# LTC6803-3.net
KiCad netlist of a schematic drawn in Altium Designer
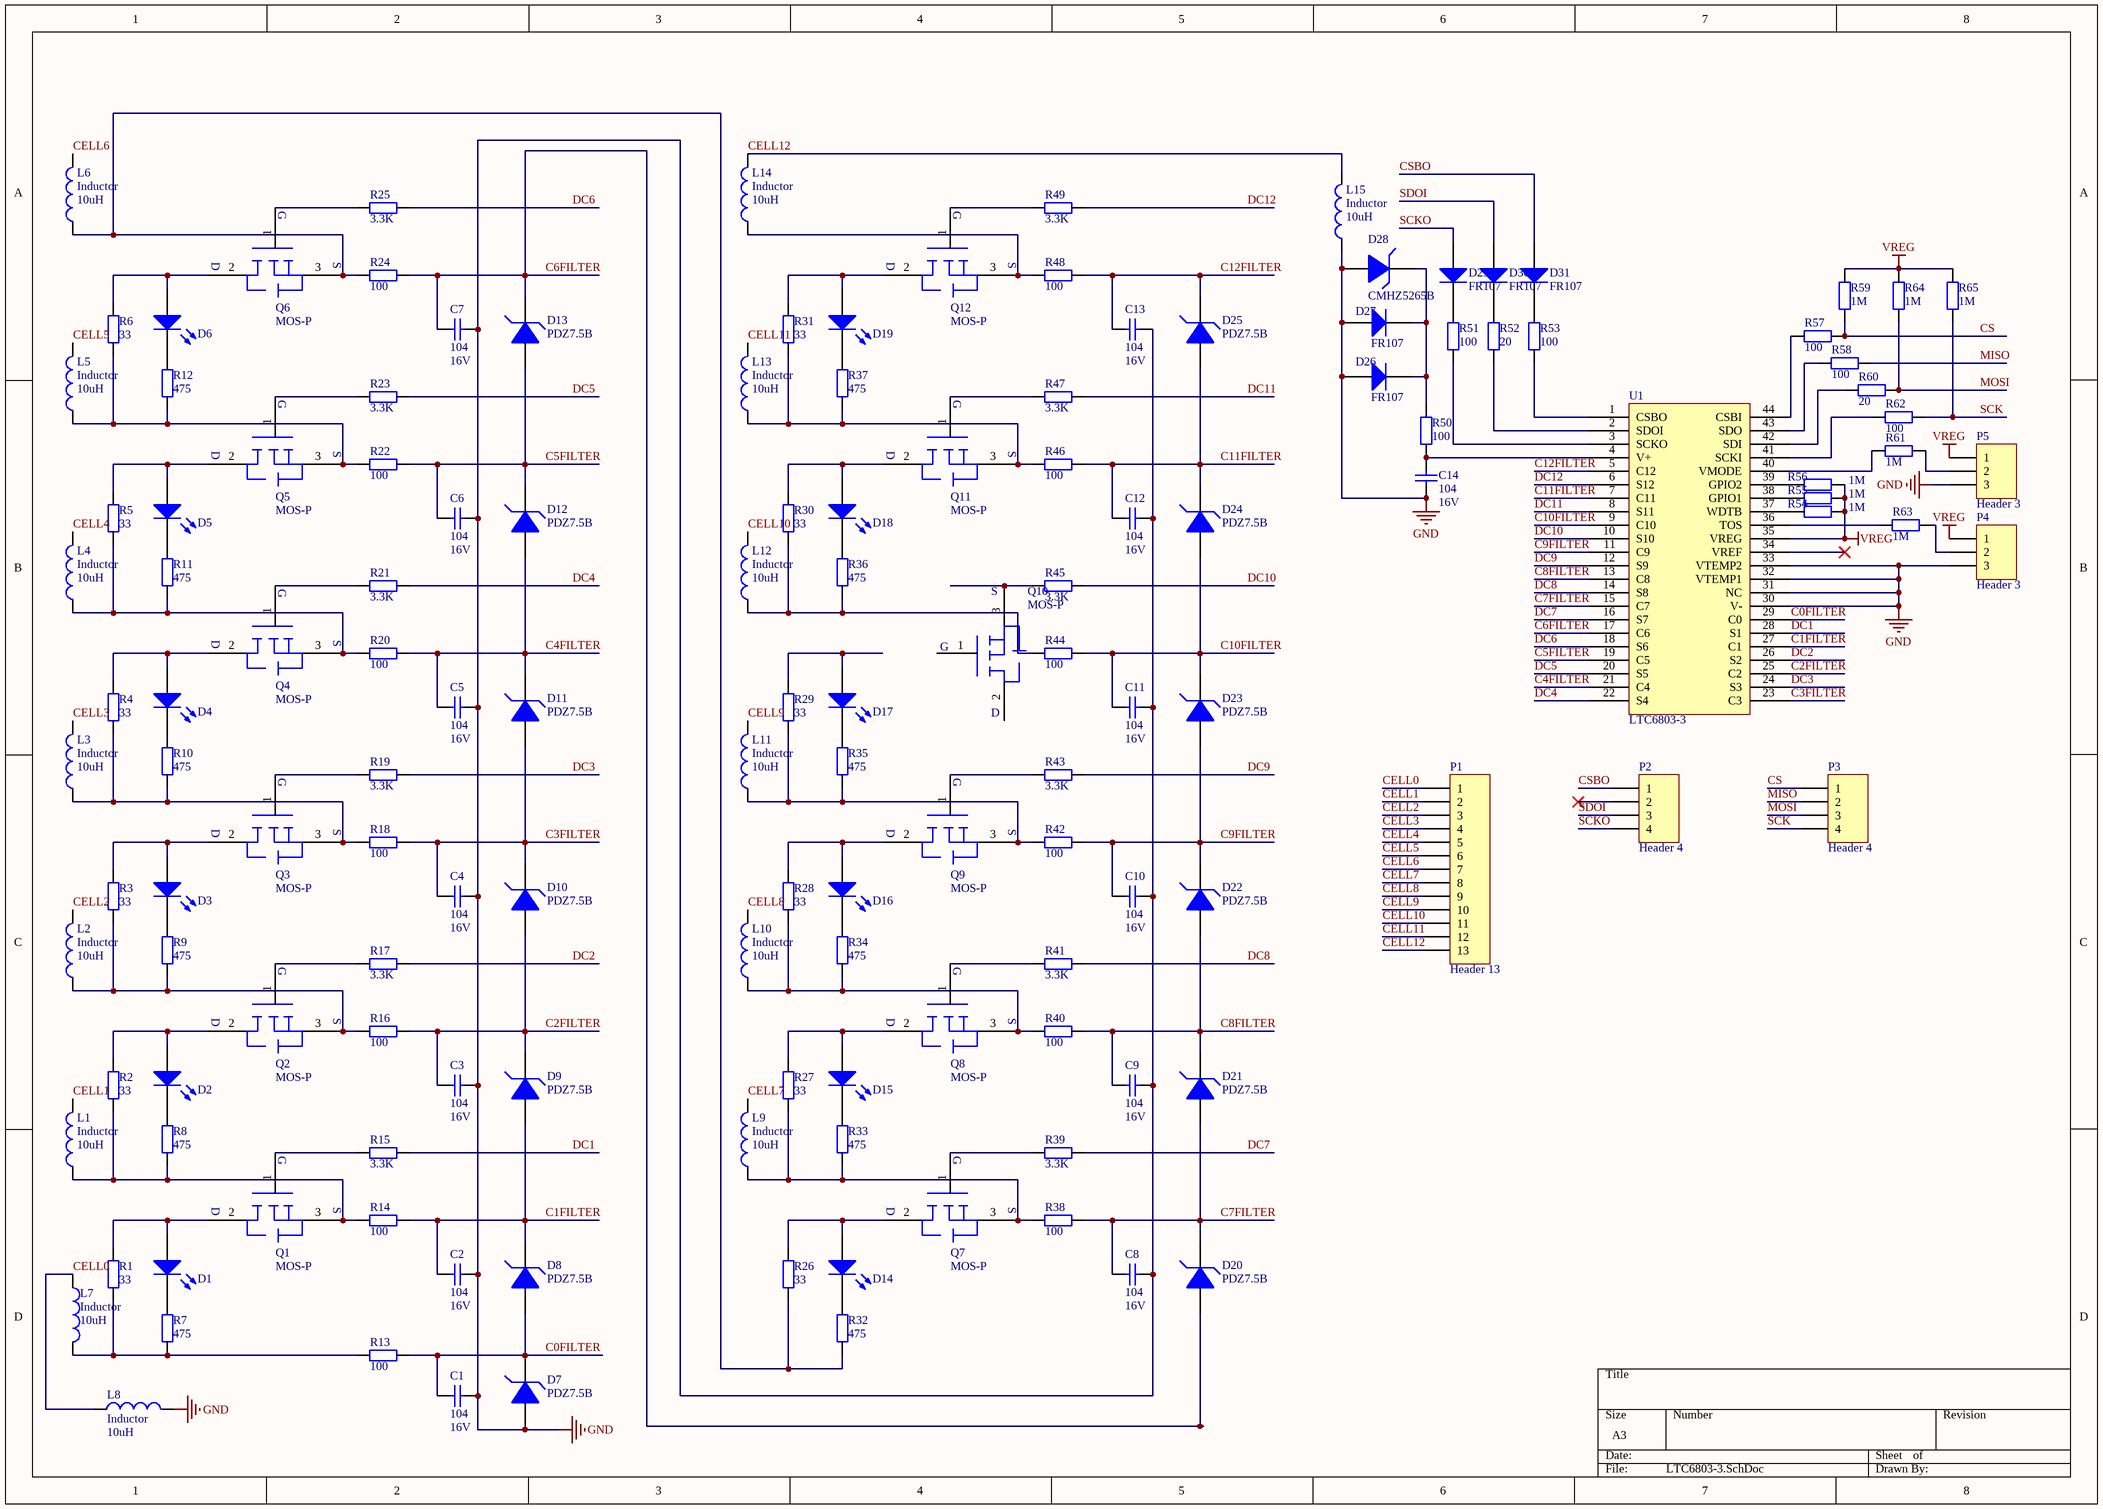
[diagram p0: LTC6803-3.SchDoc]

(export (version "E")
  (design (tool "Eeschema 10.0.6"))
  (components
    (comp (ref "C1")
      (value "104")
      (footprint "1206")
      (fields (field (name "PRESSURE VOLTAGE") "16V") (field (name "Comment") "Cap"))
      (libsource (lib "自动化研究所集成库20170403") (part "Cap"))
    )
    (comp (ref "C2")
      (value "104")
      (footprint "1206")
      (fields (field (name "PRESSURE VOLTAGE") "16V") (field (name "Comment") "Cap"))
      (libsource (lib "自动化研究所集成库20170403") (part "Cap"))
    )
    (comp (ref "C3")
      (value "104")
      (footprint "1206")
      (fields (field (name "PRESSURE VOLTAGE") "16V") (field (name "Comment") "Cap"))
      (libsource (lib "自动化研究所集成库20170403") (part "Cap"))
    )
    (comp (ref "C4")
      (value "104")
      (footprint "1206")
      (fields (field (name "PRESSURE VOLTAGE") "16V") (field (name "Comment") "Cap"))
      (libsource (lib "自动化研究所集成库20170403") (part "Cap"))
    )
    (comp (ref "C5")
      (value "104")
      (footprint "1206")
      (fields (field (name "PRESSURE VOLTAGE") "16V") (field (name "Comment") "Cap"))
      (libsource (lib "自动化研究所集成库20170403") (part "Cap"))
    )
    (comp (ref "C6")
      (value "104")
      (footprint "1206")
      (fields (field (name "PRESSURE VOLTAGE") "16V") (field (name "Comment") "Cap"))
      (libsource (lib "自动化研究所集成库20170403") (part "Cap"))
    )
    (comp (ref "C7")
      (value "104")
      (footprint "1206")
      (fields (field (name "PRESSURE VOLTAGE") "16V") (field (name "Comment") "Cap"))
      (libsource (lib "自动化研究所集成库20170403") (part "Cap"))
    )
    (comp (ref "C8")
      (value "104")
      (footprint "1206")
      (fields (field (name "PRESSURE VOLTAGE") "16V") (field (name "Comment") "Cap"))
      (libsource (lib "自动化研究所集成库20170403") (part "Cap"))
    )
    (comp (ref "C9")
      (value "104")
      (footprint "1206")
      (fields (field (name "PRESSURE VOLTAGE") "16V") (field (name "Comment") "Cap"))
      (libsource (lib "自动化研究所集成库20170403") (part "Cap"))
    )
    (comp (ref "C10")
      (value "104")
      (footprint "1206")
      (fields (field (name "PRESSURE VOLTAGE") "16V") (field (name "Comment") "Cap"))
      (libsource (lib "自动化研究所集成库20170403") (part "Cap"))
    )
    (comp (ref "C11")
      (value "104")
      (footprint "1206")
      (fields (field (name "PRESSURE VOLTAGE") "16V") (field (name "Comment") "Cap"))
      (libsource (lib "自动化研究所集成库20170403") (part "Cap"))
    )
    (comp (ref "C12")
      (value "104")
      (footprint "1206")
      (fields (field (name "PRESSURE VOLTAGE") "16V") (field (name "Comment") "Cap"))
      (libsource (lib "自动化研究所集成库20170403") (part "Cap"))
    )
    (comp (ref "C13")
      (value "104")
      (footprint "1206")
      (fields (field (name "PRESSURE VOLTAGE") "16V") (field (name "Comment") "Cap"))
      (libsource (lib "自动化研究所集成库20170403") (part "Cap"))
    )
    (comp (ref "C14")
      (value "104")
      (footprint "1206")
      (fields (field (name "PRESSURE VOLTAGE") "16V") (field (name "Comment") "Cap"))
      (libsource (lib "自动化研究所集成库20170403") (part "Cap"))
    )
    (comp (ref "D1") (value "LED") (footprint "LED_0805") (libsource (lib "自动化研究所集成库20170403") (part "LED")))
    (comp (ref "D2") (value "LED") (footprint "LED_0805") (libsource (lib "自动化研究所集成库20170403") (part "LED")))
    (comp (ref "D3") (value "LED") (footprint "LED_0805") (libsource (lib "自动化研究所集成库20170403") (part "LED")))
    (comp (ref "D4") (value "LED") (footprint "LED_0805") (libsource (lib "自动化研究所集成库20170403") (part "LED")))
    (comp (ref "D5") (value "LED") (footprint "LED_0805") (libsource (lib "自动化研究所集成库20170403") (part "LED")))
    (comp (ref "D6") (value "LED") (footprint "LED_0805") (libsource (lib "自动化研究所集成库20170403") (part "LED")))
    (comp (ref "D7")
      (value "PDZ7.5B")
      (footprint "SODFL250X110-2N")
      (libsource (lib "自动化研究所集成库20170403") (part "PDZ7.5B"))
    )
    (comp (ref "D8")
      (value "PDZ7.5B")
      (footprint "SODFL250X110-2N")
      (libsource (lib "自动化研究所集成库20170403") (part "PDZ7.5B"))
    )
    (comp (ref "D9")
      (value "PDZ7.5B")
      (footprint "SODFL250X110-2N")
      (libsource (lib "自动化研究所集成库20170403") (part "PDZ7.5B"))
    )
    (comp (ref "D10")
      (value "PDZ7.5B")
      (footprint "SODFL250X110-2N")
      (libsource (lib "自动化研究所集成库20170403") (part "PDZ7.5B"))
    )
    (comp (ref "D11")
      (value "PDZ7.5B")
      (footprint "SODFL250X110-2N")
      (libsource (lib "自动化研究所集成库20170403") (part "PDZ7.5B"))
    )
    (comp (ref "D12")
      (value "PDZ7.5B")
      (footprint "SODFL250X110-2N")
      (libsource (lib "自动化研究所集成库20170403") (part "PDZ7.5B"))
    )
    (comp (ref "D13")
      (value "PDZ7.5B")
      (footprint "SODFL250X110-2N")
      (libsource (lib "自动化研究所集成库20170403") (part "PDZ7.5B"))
    )
    (comp (ref "D14") (value "LED") (footprint "LED_0805") (libsource (lib "自动化研究所集成库20170403") (part "LED")))
    (comp (ref "D15") (value "LED") (footprint "LED_0805") (libsource (lib "自动化研究所集成库20170403") (part "LED")))
    (comp (ref "D16") (value "LED") (footprint "LED_0805") (libsource (lib "自动化研究所集成库20170403") (part "LED")))
    (comp (ref "D17") (value "LED") (footprint "LED_0805") (libsource (lib "自动化研究所集成库20170403") (part "LED")))
    (comp (ref "D18") (value "LED") (footprint "LED_0805") (libsource (lib "自动化研究所集成库20170403") (part "LED")))
    (comp (ref "D19") (value "LED") (footprint "LED_0805") (libsource (lib "自动化研究所集成库20170403") (part "LED")))
    (comp (ref "D20")
      (value "PDZ7.5B")
      (footprint "SODFL250X110-2N")
      (libsource (lib "自动化研究所集成库20170403") (part "PDZ7.5B"))
    )
    (comp (ref "D21")
      (value "PDZ7.5B")
      (footprint "SODFL250X110-2N")
      (libsource (lib "自动化研究所集成库20170403") (part "PDZ7.5B"))
    )
    (comp (ref "D22")
      (value "PDZ7.5B")
      (footprint "SODFL250X110-2N")
      (libsource (lib "自动化研究所集成库20170403") (part "PDZ7.5B"))
    )
    (comp (ref "D23")
      (value "PDZ7.5B")
      (footprint "SODFL250X110-2N")
      (libsource (lib "自动化研究所集成库20170403") (part "PDZ7.5B"))
    )
    (comp (ref "D24")
      (value "PDZ7.5B")
      (footprint "SODFL250X110-2N")
      (libsource (lib "自动化研究所集成库20170403") (part "PDZ7.5B"))
    )
    (comp (ref "D25")
      (value "PDZ7.5B")
      (footprint "SODFL250X110-2N")
      (libsource (lib "自动化研究所集成库20170403") (part "PDZ7.5B"))
    )
    (comp (ref "D26")
      (value "FR107")
      (footprint "DIO-214")
      (libsource (lib "自动化研究所集成库20170403") (part "二极管"))
    )
    (comp (ref "D27")
      (value "FR107")
      (footprint "DIO-214")
      (libsource (lib "自动化研究所集成库20170403") (part "二极管"))
    )
    (comp (ref "D28")
      (value "CMHZ5265B")
      (footprint "SODFL372X135-2N")
      (description "62V Zener Diode")
      (libsource (lib "自动化研究所集成库20170403") (part "CMHZ5265B"))
    )
    (comp (ref "D29")
      (value "FR107")
      (footprint "DIO-214")
      (libsource (lib "自动化研究所集成库20170403") (part "二极管"))
    )
    (comp (ref "D30")
      (value "FR107")
      (footprint "DIO-214")
      (libsource (lib "自动化研究所集成库20170403") (part "二极管"))
    )
    (comp (ref "D31")
      (value "FR107")
      (footprint "DIO-214")
      (libsource (lib "自动化研究所集成库20170403") (part "二极管"))
    )
    (comp (ref "L1")
      (value "Inductor")
      (footprint "0805_Inductor")
      (fields (field (name "ALTIUM_VALUE") "10uH"))
      (libsource (lib "自动化研究所集成库20170403") (part "Inductor"))
    )
    (comp (ref "L2")
      (value "Inductor")
      (footprint "0805_Inductor")
      (fields (field (name "ALTIUM_VALUE") "10uH"))
      (libsource (lib "自动化研究所集成库20170403") (part "Inductor"))
    )
    (comp (ref "L3")
      (value "Inductor")
      (footprint "0805_Inductor")
      (fields (field (name "ALTIUM_VALUE") "10uH"))
      (libsource (lib "自动化研究所集成库20170403") (part "Inductor"))
    )
    (comp (ref "L4")
      (value "Inductor")
      (footprint "0805_Inductor")
      (fields (field (name "ALTIUM_VALUE") "10uH"))
      (libsource (lib "自动化研究所集成库20170403") (part "Inductor"))
    )
    (comp (ref "L5")
      (value "Inductor")
      (footprint "0805_Inductor")
      (fields (field (name "ALTIUM_VALUE") "10uH"))
      (libsource (lib "自动化研究所集成库20170403") (part "Inductor"))
    )
    (comp (ref "L6")
      (value "Inductor")
      (footprint "0805_Inductor")
      (fields (field (name "ALTIUM_VALUE") "10uH"))
      (libsource (lib "自动化研究所集成库20170403") (part "Inductor"))
    )
    (comp (ref "L7")
      (value "Inductor")
      (footprint "0805_Inductor")
      (fields (field (name "ALTIUM_VALUE") "10uH"))
      (libsource (lib "自动化研究所集成库20170403") (part "Inductor"))
    )
    (comp (ref "L8")
      (value "Inductor")
      (footprint "0805_Inductor")
      (fields (field (name "ALTIUM_VALUE") "10uH"))
      (libsource (lib "自动化研究所集成库20170403") (part "Inductor"))
    )
    (comp (ref "L9")
      (value "Inductor")
      (footprint "0805_Inductor")
      (fields (field (name "ALTIUM_VALUE") "10uH"))
      (libsource (lib "自动化研究所集成库20170403") (part "Inductor"))
    )
    (comp (ref "L10")
      (value "Inductor")
      (footprint "0805_Inductor")
      (fields (field (name "ALTIUM_VALUE") "10uH"))
      (libsource (lib "自动化研究所集成库20170403") (part "Inductor"))
    )
    (comp (ref "L11")
      (value "Inductor")
      (footprint "0805_Inductor")
      (fields (field (name "ALTIUM_VALUE") "10uH"))
      (libsource (lib "自动化研究所集成库20170403") (part "Inductor"))
    )
    (comp (ref "L12")
      (value "Inductor")
      (footprint "0805_Inductor")
      (fields (field (name "ALTIUM_VALUE") "10uH"))
      (libsource (lib "自动化研究所集成库20170403") (part "Inductor"))
    )
    (comp (ref "L13")
      (value "Inductor")
      (footprint "0805_Inductor")
      (fields (field (name "ALTIUM_VALUE") "10uH"))
      (libsource (lib "自动化研究所集成库20170403") (part "Inductor"))
    )
    (comp (ref "L14")
      (value "Inductor")
      (footprint "0805_Inductor")
      (fields (field (name "ALTIUM_VALUE") "10uH"))
      (libsource (lib "自动化研究所集成库20170403") (part "Inductor"))
    )
    (comp (ref "L15")
      (value "Inductor")
      (footprint "0805_Inductor")
      (fields (field (name "ALTIUM_VALUE") "10uH"))
      (libsource (lib "自动化研究所集成库20170403") (part "Inductor"))
    )
    (comp (ref "P1")
      (value "Header 13")
      (footprint "HDR1X13")
      (description "Header, 13-Pin")
      (libsource (lib "Miscellaneous Connectors") (part "Header 13"))
    )
    (comp (ref "P2")
      (value "Header 4")
      (footprint "HDR1X4")
      (description "Header, 4-Pin")
      (libsource (lib "Miscellaneous Connectors") (part "Header 4"))
    )
    (comp (ref "P3")
      (value "Header 4")
      (footprint "HDR1X4")
      (description "Header, 4-Pin")
      (libsource (lib "Miscellaneous Connectors") (part "Header 4"))
    )
    (comp (ref "P4")
      (value "Header 3")
      (footprint "HDR1X3")
      (description "Header, 3-Pin")
      (libsource (lib "Miscellaneous Connectors") (part "Header 3"))
    )
    (comp (ref "P5")
      (value "Header 3")
      (footprint "HDR1X3")
      (description "Header, 3-Pin")
      (libsource (lib "Miscellaneous Connectors") (part "Header 3"))
    )
    (comp (ref "Q1")
      (value "MOS-P")
      (footprint "SOT23_N")
      (libsource (lib "自动化研究所集成库20170403") (part "MOS-P"))
    )
    (comp (ref "Q2")
      (value "MOS-P")
      (footprint "SOT23_N")
      (libsource (lib "自动化研究所集成库20170403") (part "MOS-P"))
    )
    (comp (ref "Q3")
      (value "MOS-P")
      (footprint "SOT23_N")
      (libsource (lib "自动化研究所集成库20170403") (part "MOS-P"))
    )
    (comp (ref "Q4")
      (value "MOS-P")
      (footprint "SOT23_N")
      (libsource (lib "自动化研究所集成库20170403") (part "MOS-P"))
    )
    (comp (ref "Q5")
      (value "MOS-P")
      (footprint "SOT23_N")
      (libsource (lib "自动化研究所集成库20170403") (part "MOS-P"))
    )
    (comp (ref "Q6")
      (value "MOS-P")
      (footprint "SOT23_N")
      (libsource (lib "自动化研究所集成库20170403") (part "MOS-P"))
    )
    (comp (ref "Q7")
      (value "MOS-P")
      (footprint "SOT23_N")
      (libsource (lib "自动化研究所集成库20170403") (part "MOS-P"))
    )
    (comp (ref "Q8")
      (value "MOS-P")
      (footprint "SOT23_N")
      (libsource (lib "自动化研究所集成库20170403") (part "MOS-P"))
    )
    (comp (ref "Q9")
      (value "MOS-P")
      (footprint "SOT23_N")
      (libsource (lib "自动化研究所集成库20170403") (part "MOS-P"))
    )
    (comp (ref "Q10")
      (value "MOS-P")
      (footprint "SOT23_N")
      (libsource (lib "自动化研究所集成库20170403") (part "MOS-P"))
    )
    (comp (ref "Q11")
      (value "MOS-P")
      (footprint "SOT23_N")
      (libsource (lib "自动化研究所集成库20170403") (part "MOS-P"))
    )
    (comp (ref "Q12")
      (value "MOS-P")
      (footprint "SOT23_N")
      (libsource (lib "自动化研究所集成库20170403") (part "MOS-P"))
    )
    (comp (ref "R1")
      (value "33")
      (footprint "2512-RESC6332X06N")
      (fields (field (name "Comment") "Res"))
      (libsource (lib "") (part "Res_2"))
    )
    (comp (ref "R2")
      (value "33")
      (footprint "2512-RESC6332X06N")
      (fields (field (name "Comment") "Res"))
      (libsource (lib "") (part "Res_2"))
    )
    (comp (ref "R3")
      (value "33")
      (footprint "2512-RESC6332X06N")
      (fields (field (name "Comment") "Res"))
      (libsource (lib "") (part "Res_2"))
    )
    (comp (ref "R4")
      (value "33")
      (footprint "2512-RESC6332X06N")
      (fields (field (name "Comment") "Res"))
      (libsource (lib "") (part "Res_2"))
    )
    (comp (ref "R5")
      (value "33")
      (footprint "2512-RESC6332X06N")
      (fields (field (name "Comment") "Res"))
      (libsource (lib "") (part "Res_2"))
    )
    (comp (ref "R6")
      (value "33")
      (footprint "2512-RESC6332X06N")
      (fields (field (name "Comment") "Res"))
      (libsource (lib "") (part "Res_2"))
    )
    (comp (ref "R7")
      (value "475")
      (footprint "0805")
      (fields (field (name "Comment") "Res"))
      (libsource (lib "") (part "Res_2"))
    )
    (comp (ref "R8")
      (value "475")
      (footprint "0805")
      (fields (field (name "Comment") "Res"))
      (libsource (lib "") (part "Res_2"))
    )
    (comp (ref "R9")
      (value "475")
      (footprint "0805")
      (fields (field (name "Comment") "Res"))
      (libsource (lib "") (part "Res_2"))
    )
    (comp (ref "R10")
      (value "475")
      (footprint "0805")
      (fields (field (name "Comment") "Res"))
      (libsource (lib "") (part "Res_2"))
    )
    (comp (ref "R11")
      (value "475")
      (footprint "0805")
      (fields (field (name "Comment") "Res"))
      (libsource (lib "") (part "Res_2"))
    )
    (comp (ref "R12")
      (value "475")
      (footprint "0805")
      (fields (field (name "Comment") "Res"))
      (libsource (lib "") (part "Res_2"))
    )
    (comp (ref "R13")
      (value "100")
      (footprint "0805")
      (fields (field (name "Comment") "Res"))
      (libsource (lib "") (part "Res_1"))
    )
    (comp (ref "R14")
      (value "100")
      (footprint "0805")
      (fields (field (name "Comment") "Res"))
      (libsource (lib "") (part "Res_1"))
    )
    (comp (ref "R15")
      (value "3.3K")
      (footprint "0805")
      (fields (field (name "Comment") "Res"))
      (libsource (lib "") (part "Res_1"))
    )
    (comp (ref "R16")
      (value "100")
      (footprint "0805")
      (fields (field (name "Comment") "Res"))
      (libsource (lib "") (part "Res_1"))
    )
    (comp (ref "R17")
      (value "3.3K")
      (footprint "0805")
      (fields (field (name "Comment") "Res"))
      (libsource (lib "") (part "Res_1"))
    )
    (comp (ref "R18")
      (value "100")
      (footprint "0805")
      (fields (field (name "Comment") "Res"))
      (libsource (lib "") (part "Res_1"))
    )
    (comp (ref "R19")
      (value "3.3K")
      (footprint "0805")
      (fields (field (name "Comment") "Res"))
      (libsource (lib "") (part "Res_1"))
    )
    (comp (ref "R20")
      (value "100")
      (footprint "0805")
      (fields (field (name "Comment") "Res"))
      (libsource (lib "") (part "Res_1"))
    )
    (comp (ref "R21")
      (value "3.3K")
      (footprint "0805")
      (fields (field (name "Comment") "Res"))
      (libsource (lib "") (part "Res_1"))
    )
    (comp (ref "R22")
      (value "100")
      (footprint "0805")
      (fields (field (name "Comment") "Res"))
      (libsource (lib "") (part "Res_1"))
    )
    (comp (ref "R23")
      (value "3.3K")
      (footprint "0805")
      (fields (field (name "Comment") "Res"))
      (libsource (lib "") (part "Res_1"))
    )
    (comp (ref "R24")
      (value "100")
      (footprint "0805")
      (fields (field (name "Comment") "Res"))
      (libsource (lib "") (part "Res_1"))
    )
    (comp (ref "R25")
      (value "3.3K")
      (footprint "0805")
      (fields (field (name "Comment") "Res"))
      (libsource (lib "") (part "Res_1"))
    )
    (comp (ref "R26")
      (value "33")
      (footprint "2512-RESC6332X06N")
      (fields (field (name "Comment") "Res"))
      (libsource (lib "") (part "Res_2"))
    )
    (comp (ref "R27")
      (value "33")
      (footprint "2512-RESC6332X06N")
      (fields (field (name "Comment") "Res"))
      (libsource (lib "") (part "Res_2"))
    )
    (comp (ref "R28")
      (value "33")
      (footprint "2512-RESC6332X06N")
      (fields (field (name "Comment") "Res"))
      (libsource (lib "") (part "Res_2"))
    )
    (comp (ref "R29")
      (value "33")
      (footprint "2512-RESC6332X06N")
      (fields (field (name "Comment") "Res"))
      (libsource (lib "") (part "Res_2"))
    )
    (comp (ref "R30")
      (value "33")
      (footprint "2512-RESC6332X06N")
      (fields (field (name "Comment") "Res"))
      (libsource (lib "") (part "Res_2"))
    )
    (comp (ref "R31")
      (value "33")
      (footprint "2512-RESC6332X06N")
      (fields (field (name "Comment") "Res"))
      (libsource (lib "") (part "Res_2"))
    )
    (comp (ref "R32")
      (value "475")
      (footprint "0805")
      (fields (field (name "Comment") "Res"))
      (libsource (lib "") (part "Res_2"))
    )
    (comp (ref "R33")
      (value "475")
      (footprint "0805")
      (fields (field (name "Comment") "Res"))
      (libsource (lib "") (part "Res_2"))
    )
    (comp (ref "R34")
      (value "475")
      (footprint "0805")
      (fields (field (name "Comment") "Res"))
      (libsource (lib "") (part "Res_2"))
    )
    (comp (ref "R35")
      (value "475")
      (footprint "0805")
      (fields (field (name "Comment") "Res"))
      (libsource (lib "") (part "Res_2"))
    )
    (comp (ref "R36")
      (value "475")
      (footprint "0805")
      (fields (field (name "Comment") "Res"))
      (libsource (lib "") (part "Res_2"))
    )
    (comp (ref "R37")
      (value "475")
      (footprint "0805")
      (fields (field (name "Comment") "Res"))
      (libsource (lib "") (part "Res_2"))
    )
    (comp (ref "R38")
      (value "100")
      (footprint "0805")
      (fields (field (name "Comment") "Res"))
      (libsource (lib "") (part "Res_1"))
    )
    (comp (ref "R39")
      (value "3.3K")
      (footprint "0805")
      (fields (field (name "Comment") "Res"))
      (libsource (lib "") (part "Res_1"))
    )
    (comp (ref "R40")
      (value "100")
      (footprint "0805")
      (fields (field (name "Comment") "Res"))
      (libsource (lib "") (part "Res_1"))
    )
    (comp (ref "R41")
      (value "3.3K")
      (footprint "0805")
      (fields (field (name "Comment") "Res"))
      (libsource (lib "") (part "Res_1"))
    )
    (comp (ref "R42")
      (value "100")
      (footprint "0805")
      (fields (field (name "Comment") "Res"))
      (libsource (lib "") (part "Res_1"))
    )
    (comp (ref "R43")
      (value "3.3K")
      (footprint "0805")
      (fields (field (name "Comment") "Res"))
      (libsource (lib "") (part "Res_1"))
    )
    (comp (ref "R44")
      (value "100")
      (footprint "0805")
      (fields (field (name "Comment") "Res"))
      (libsource (lib "") (part "Res_1"))
    )
    (comp (ref "R45")
      (value "3.3K")
      (footprint "0805")
      (fields (field (name "Comment") "Res"))
      (libsource (lib "") (part "Res_1"))
    )
    (comp (ref "R46")
      (value "100")
      (footprint "0805")
      (fields (field (name "Comment") "Res"))
      (libsource (lib "") (part "Res_1"))
    )
    (comp (ref "R47")
      (value "3.3K")
      (footprint "0805")
      (fields (field (name "Comment") "Res"))
      (libsource (lib "") (part "Res_1"))
    )
    (comp (ref "R48")
      (value "100")
      (footprint "0805")
      (fields (field (name "Comment") "Res"))
      (libsource (lib "") (part "Res_1"))
    )
    (comp (ref "R49")
      (value "3.3K")
      (footprint "0805")
      (fields (field (name "Comment") "Res"))
      (libsource (lib "") (part "Res_1"))
    )
    (comp (ref "R50")
      (value "100")
      (footprint "0805")
      (fields (field (name "Comment") "Res"))
      (libsource (lib "") (part "Res_2"))
    )
    (comp (ref "R51")
      (value "100")
      (footprint "0805")
      (fields (field (name "Comment") "Res"))
      (libsource (lib "") (part "Res_2"))
    )
    (comp (ref "R52")
      (value "20")
      (footprint "0805")
      (fields (field (name "Comment") "Res"))
      (libsource (lib "") (part "Res_2"))
    )
    (comp (ref "R53")
      (value "100")
      (footprint "0805")
      (fields (field (name "Comment") "Res"))
      (libsource (lib "") (part "Res_2"))
    )
    (comp (ref "R54")
      (value "1M")
      (footprint "0805")
      (fields (field (name "Comment") "Res"))
      (libsource (lib "自动化研究所集成库20170403") (part "Res"))
    )
    (comp (ref "R55")
      (value "1M")
      (footprint "0805")
      (fields (field (name "Comment") "Res"))
      (libsource (lib "自动化研究所集成库20170403") (part "Res"))
    )
    (comp (ref "R56")
      (value "1M")
      (footprint "0805")
      (fields (field (name "Comment") "Res"))
      (libsource (lib "自动化研究所集成库20170403") (part "Res"))
    )
    (comp (ref "R57")
      (value "100")
      (footprint "0805")
      (fields (field (name "Comment") "Res"))
      (libsource (lib "自动化研究所集成库20170403") (part "Res"))
    )
    (comp (ref "R58")
      (value "100")
      (footprint "0805")
      (fields (field (name "Comment") "Res"))
      (libsource (lib "自动化研究所集成库20170403") (part "Res"))
    )
    (comp (ref "R59")
      (value "1M")
      (footprint "0805")
      (fields (field (name "Comment") "Res"))
      (libsource (lib "") (part "Res_3"))
    )
    (comp (ref "R60")
      (value "20")
      (footprint "0805")
      (fields (field (name "Comment") "Res"))
      (libsource (lib "自动化研究所集成库20170403") (part "Res"))
    )
    (comp (ref "R61")
      (value "1M")
      (footprint "0805")
      (fields (field (name "Comment") "Res"))
      (libsource (lib "自动化研究所集成库20170403") (part "Res"))
    )
    (comp (ref "R62")
      (value "100")
      (footprint "0805")
      (fields (field (name "Comment") "Res"))
      (libsource (lib "自动化研究所集成库20170403") (part "Res"))
    )
    (comp (ref "R63")
      (value "1M")
      (footprint "0805")
      (fields (field (name "Comment") "Res"))
      (libsource (lib "自动化研究所集成库20170403") (part "Res"))
    )
    (comp (ref "R64")
      (value "1M")
      (footprint "0805")
      (fields (field (name "Comment") "Res"))
      (libsource (lib "") (part "Res_3"))
    )
    (comp (ref "R65")
      (value "1M")
      (footprint "0805")
      (fields (field (name "Comment") "Res"))
      (libsource (lib "") (part "Res_3"))
    )
    (comp (ref "U1")
      (value "LTC6803-3")
      (footprint "SSOP50P780X200-44N")
      (libsource (lib "自动化研究所集成库20170403") (part "LTC6803-3"))
    )
  )
  (nets
    (net (code "1") (name "/C0FILTER") (class "Default")
      (node (ref "C1") (pin "1") (pinfunction "1_1") (pintype "passive"))
      (node (ref "D7") (pin "2") (pinfunction "K_2") (pintype "passive"))
      (node (ref "D8") (pin "1") (pinfunction "A_1") (pintype "passive"))
      (node (ref "R13") (pin "2") (pinfunction "2_2") (pintype "passive"))
      (node (ref "U1") (pin "29") (pinfunction "C0_29") (pintype "passive"))
    )
    (net (code "2") (name "/C1FILTER") (class "Default")
      (node (ref "C2") (pin "1") (pinfunction "1_1") (pintype "passive"))
      (node (ref "D8") (pin "2") (pinfunction "K_2") (pintype "passive"))
      (node (ref "D9") (pin "1") (pinfunction "A_1") (pintype "passive"))
      (node (ref "R14") (pin "2") (pinfunction "2_2") (pintype "passive"))
      (node (ref "U1") (pin "27") (pinfunction "C1_27") (pintype "passive"))
    )
    (net (code "3") (name "/C2FILTER") (class "Default")
      (node (ref "C3") (pin "1") (pinfunction "1_1") (pintype "passive"))
      (node (ref "D10") (pin "1") (pinfunction "A_1") (pintype "passive"))
      (node (ref "D9") (pin "2") (pinfunction "K_2") (pintype "passive"))
      (node (ref "R16") (pin "2") (pinfunction "2_2") (pintype "passive"))
      (node (ref "U1") (pin "25") (pinfunction "C2_25") (pintype "passive"))
    )
    (net (code "4") (name "/C3FILTER") (class "Default")
      (node (ref "C4") (pin "1") (pinfunction "1_1") (pintype "passive"))
      (node (ref "D10") (pin "2") (pinfunction "K_2") (pintype "passive"))
      (node (ref "D11") (pin "1") (pinfunction "A_1") (pintype "passive"))
      (node (ref "R18") (pin "2") (pinfunction "2_2") (pintype "passive"))
      (node (ref "U1") (pin "23") (pinfunction "C3_23") (pintype "passive"))
    )
    (net (code "5") (name "/C4FILTER") (class "Default")
      (node (ref "C5") (pin "1") (pinfunction "1_1") (pintype "passive"))
      (node (ref "D11") (pin "2") (pinfunction "K_2") (pintype "passive"))
      (node (ref "D12") (pin "1") (pinfunction "A_1") (pintype "passive"))
      (node (ref "R20") (pin "2") (pinfunction "2_2") (pintype "passive"))
      (node (ref "U1") (pin "21") (pinfunction "C4_21") (pintype "passive"))
    )
    (net (code "6") (name "/C5FILTER") (class "Default")
      (node (ref "C6") (pin "1") (pinfunction "1_1") (pintype "passive"))
      (node (ref "D12") (pin "2") (pinfunction "K_2") (pintype "passive"))
      (node (ref "D13") (pin "1") (pinfunction "A_1") (pintype "passive"))
      (node (ref "R22") (pin "2") (pinfunction "2_2") (pintype "passive"))
      (node (ref "U1") (pin "19") (pinfunction "C5_19") (pintype "passive"))
    )
    (net (code "7") (name "/C6FILTER") (class "Default")
      (node (ref "C7") (pin "1") (pinfunction "1_1") (pintype "passive"))
      (node (ref "D13") (pin "2") (pinfunction "K_2") (pintype "passive"))
      (node (ref "D20") (pin "1") (pinfunction "A_1") (pintype "passive"))
      (node (ref "R24") (pin "2") (pinfunction "2_2") (pintype "passive"))
      (node (ref "U1") (pin "17") (pinfunction "C6_17") (pintype "passive"))
    )
    (net (code "8") (name "/C7FILTER") (class "Default")
      (node (ref "C8") (pin "1") (pinfunction "1_1") (pintype "passive"))
      (node (ref "D20") (pin "2") (pinfunction "K_2") (pintype "passive"))
      (node (ref "D21") (pin "1") (pinfunction "A_1") (pintype "passive"))
      (node (ref "R38") (pin "2") (pinfunction "2_2") (pintype "passive"))
      (node (ref "U1") (pin "15") (pinfunction "C7_15") (pintype "passive"))
    )
    (net (code "9") (name "/C8FILTER") (class "Default")
      (node (ref "C9") (pin "1") (pinfunction "1_1") (pintype "passive"))
      (node (ref "D21") (pin "2") (pinfunction "K_2") (pintype "passive"))
      (node (ref "D22") (pin "1") (pinfunction "A_1") (pintype "passive"))
      (node (ref "R40") (pin "2") (pinfunction "2_2") (pintype "passive"))
      (node (ref "U1") (pin "13") (pinfunction "C8_13") (pintype "passive"))
    )
    (net (code "10") (name "/C9FILTER") (class "Default")
      (node (ref "C10") (pin "1") (pinfunction "1_1") (pintype "passive"))
      (node (ref "D22") (pin "2") (pinfunction "K_2") (pintype "passive"))
      (node (ref "D23") (pin "1") (pinfunction "A_1") (pintype "passive"))
      (node (ref "R42") (pin "2") (pinfunction "2_2") (pintype "passive"))
      (node (ref "U1") (pin "11") (pinfunction "C9_11") (pintype "passive"))
    )
    (net (code "11") (name "/C10FILTER") (class "Default")
      (node (ref "C11") (pin "1") (pinfunction "1_1") (pintype "passive"))
      (node (ref "D23") (pin "2") (pinfunction "K_2") (pintype "passive"))
      (node (ref "D24") (pin "1") (pinfunction "A_1") (pintype "passive"))
      (node (ref "R44") (pin "2") (pinfunction "2_2") (pintype "passive"))
      (node (ref "U1") (pin "9") (pinfunction "C10_9") (pintype "passive"))
    )
    (net (code "12") (name "/C11FILTER") (class "Default")
      (node (ref "C12") (pin "1") (pinfunction "1_1") (pintype "passive"))
      (node (ref "D24") (pin "2") (pinfunction "K_2") (pintype "passive"))
      (node (ref "D25") (pin "1") (pinfunction "A_1") (pintype "passive"))
      (node (ref "R46") (pin "2") (pinfunction "2_2") (pintype "passive"))
      (node (ref "U1") (pin "7") (pinfunction "C11_7") (pintype "passive"))
    )
    (net (code "13") (name "/C12FILTER") (class "Default")
      (node (ref "C13") (pin "1") (pinfunction "1_1") (pintype "passive"))
      (node (ref "D25") (pin "2") (pinfunction "K_2") (pintype "passive"))
      (node (ref "R48") (pin "2") (pinfunction "2_2") (pintype "passive"))
      (node (ref "U1") (pin "5") (pinfunction "C12_5") (pintype "passive"))
    )
    (net (code "14") (name "/CELL0") (class "Default")
      (node (ref "L7") (pin "1") (pinfunction "1_1") (pintype "passive"))
      (node (ref "L8") (pin "1") (pinfunction "1_1") (pintype "passive"))
      (node (ref "P1") (pin "1") (pinfunction "1_1") (pintype "passive"))
    )
    (net (code "15") (name "/CELL1") (class "Default")
      (node (ref "L1") (pin "2") (pinfunction "2_2") (pintype "passive"))
      (node (ref "P1") (pin "2") (pinfunction "2_2") (pintype "passive"))
    )
    (net (code "16") (name "/CELL2") (class "Default")
      (node (ref "L2") (pin "2") (pinfunction "2_2") (pintype "passive"))
      (node (ref "P1") (pin "3") (pinfunction "3_3") (pintype "passive"))
    )
    (net (code "17") (name "/CELL3") (class "Default")
      (node (ref "L3") (pin "2") (pinfunction "2_2") (pintype "passive"))
      (node (ref "P1") (pin "4") (pinfunction "4_4") (pintype "passive"))
    )
    (net (code "18") (name "/CELL4") (class "Default")
      (node (ref "L4") (pin "2") (pinfunction "2_2") (pintype "passive"))
      (node (ref "P1") (pin "5") (pinfunction "5_5") (pintype "passive"))
    )
    (net (code "19") (name "/CELL5") (class "Default")
      (node (ref "L5") (pin "2") (pinfunction "2_2") (pintype "passive"))
      (node (ref "P1") (pin "6") (pinfunction "6_6") (pintype "passive"))
    )
    (net (code "20") (name "/CELL6") (class "Default")
      (node (ref "L6") (pin "2") (pinfunction "2_2") (pintype "passive"))
      (node (ref "P1") (pin "7") (pinfunction "7_7") (pintype "passive"))
    )
    (net (code "21") (name "/CELL7") (class "Default")
      (node (ref "L9") (pin "2") (pinfunction "2_2") (pintype "passive"))
      (node (ref "P1") (pin "8") (pinfunction "8_8") (pintype "passive"))
    )
    (net (code "22") (name "/CELL8") (class "Default")
      (node (ref "L10") (pin "2") (pinfunction "2_2") (pintype "passive"))
      (node (ref "P1") (pin "9") (pinfunction "9_9") (pintype "passive"))
    )
    (net (code "23") (name "/CELL9") (class "Default")
      (node (ref "L11") (pin "2") (pinfunction "2_2") (pintype "passive"))
      (node (ref "P1") (pin "10") (pinfunction "10_10") (pintype "passive"))
    )
    (net (code "24") (name "/CELL10") (class "Default")
      (node (ref "L12") (pin "2") (pinfunction "2_2") (pintype "passive"))
      (node (ref "P1") (pin "11") (pinfunction "11_11") (pintype "passive"))
    )
    (net (code "25") (name "/CELL11") (class "Default")
      (node (ref "L13") (pin "2") (pinfunction "2_2") (pintype "passive"))
      (node (ref "P1") (pin "12") (pinfunction "12_12") (pintype "passive"))
    )
    (net (code "26") (name "/CELL12") (class "Default")
      (node (ref "L14") (pin "2") (pinfunction "2_2") (pintype "passive"))
      (node (ref "L15") (pin "2") (pinfunction "2_2") (pintype "passive"))
      (node (ref "P1") (pin "13") (pinfunction "13_13") (pintype "passive"))
    )
    (net (code "27") (name "/CS") (class "Default")
      (node (ref "P3") (pin "1") (pinfunction "1_1") (pintype "passive"))
      (node (ref "R57") (pin "1") (pinfunction "1_1") (pintype "passive"))
      (node (ref "R59") (pin "2") (pinfunction "2_2") (pintype "passive"))
    )
    (net (code "28") (name "/CSBO") (class "Default")
      (node (ref "D31") (pin "1") (pinfunction "A_1") (pintype "passive"))
      (node (ref "P2") (pin "1") (pinfunction "1_1") (pintype "passive"))
    )
    (net (code "29") (name "/DC1") (class "Default")
      (node (ref "R15") (pin "2") (pinfunction "2_2") (pintype "passive"))
      (node (ref "U1") (pin "28") (pinfunction "S1_28") (pintype "passive"))
    )
    (net (code "30") (name "/DC2") (class "Default")
      (node (ref "R17") (pin "2") (pinfunction "2_2") (pintype "passive"))
      (node (ref "U1") (pin "26") (pinfunction "S2_26") (pintype "passive"))
    )
    (net (code "31") (name "/DC3") (class "Default")
      (node (ref "R19") (pin "2") (pinfunction "2_2") (pintype "passive"))
      (node (ref "U1") (pin "24") (pinfunction "S3_24") (pintype "passive"))
    )
    (net (code "32") (name "/DC4") (class "Default")
      (node (ref "R21") (pin "2") (pinfunction "2_2") (pintype "passive"))
      (node (ref "U1") (pin "22") (pinfunction "S4_22") (pintype "passive"))
    )
    (net (code "33") (name "/DC5") (class "Default")
      (node (ref "R23") (pin "2") (pinfunction "2_2") (pintype "passive"))
      (node (ref "U1") (pin "20") (pinfunction "S5_20") (pintype "passive"))
    )
    (net (code "34") (name "/DC6") (class "Default")
      (node (ref "R25") (pin "2") (pinfunction "2_2") (pintype "passive"))
      (node (ref "U1") (pin "18") (pinfunction "S6_18") (pintype "passive"))
    )
    (net (code "35") (name "/DC7") (class "Default")
      (node (ref "R39") (pin "2") (pinfunction "2_2") (pintype "passive"))
      (node (ref "U1") (pin "16") (pinfunction "S7_16") (pintype "passive"))
    )
    (net (code "36") (name "/DC8") (class "Default")
      (node (ref "R41") (pin "2") (pinfunction "2_2") (pintype "passive"))
      (node (ref "U1") (pin "14") (pinfunction "S8_14") (pintype "passive"))
    )
    (net (code "37") (name "/DC9") (class "Default")
      (node (ref "R43") (pin "2") (pinfunction "2_2") (pintype "passive"))
      (node (ref "U1") (pin "12") (pinfunction "S9_12") (pintype "passive"))
    )
    (net (code "38") (name "/DC10") (class "Default")
      (node (ref "R45") (pin "2") (pinfunction "2_2") (pintype "passive"))
      (node (ref "U1") (pin "10") (pinfunction "S10_10") (pintype "passive"))
    )
    (net (code "39") (name "/DC11") (class "Default")
      (node (ref "R47") (pin "2") (pinfunction "2_2") (pintype "passive"))
      (node (ref "U1") (pin "8") (pinfunction "S11_8") (pintype "passive"))
    )
    (net (code "40") (name "/DC12") (class "Default")
      (node (ref "R49") (pin "2") (pinfunction "2_2") (pintype "passive"))
      (node (ref "U1") (pin "6") (pinfunction "S12_6") (pintype "passive"))
    )
    (net (code "41") (name "/MISO") (class "Default")
      (node (ref "P3") (pin "2") (pinfunction "2_2") (pintype "passive"))
      (node (ref "R58") (pin "1") (pinfunction "1_1") (pintype "passive"))
    )
    (net (code "42") (name "/MOSI") (class "Default")
      (node (ref "P3") (pin "3") (pinfunction "3_3") (pintype "passive"))
      (node (ref "R60") (pin "1") (pinfunction "1_1") (pintype "passive"))
      (node (ref "R64") (pin "2") (pinfunction "2_2") (pintype "passive"))
    )
    (net (code "43") (name "/SCK") (class "Default")
      (node (ref "P3") (pin "4") (pinfunction "4_4") (pintype "passive"))
      (node (ref "R62") (pin "1") (pinfunction "1_1") (pintype "passive"))
      (node (ref "R65") (pin "2") (pinfunction "2_2") (pintype "passive"))
    )
    (net (code "44") (name "/SCKO") (class "Default")
      (node (ref "D29") (pin "1") (pinfunction "A_1") (pintype "passive"))
      (node (ref "P2") (pin "4") (pinfunction "4_4") (pintype "passive"))
    )
    (net (code "45") (name "/SDOI") (class "Default")
      (node (ref "D30") (pin "1") (pinfunction "A_1") (pintype "passive"))
      (node (ref "P2") (pin "3") (pinfunction "3_3") (pintype "passive"))
    )
    (net (code "46") (name "GND") (class "Default")
      (node (ref "C1") (pin "2") (pinfunction "2_2") (pintype "passive"))
      (node (ref "C10") (pin "2") (pinfunction "2_2") (pintype "passive"))
      (node (ref "C11") (pin "2") (pinfunction "2_2") (pintype "passive"))
      (node (ref "C12") (pin "2") (pinfunction "2_2") (pintype "passive"))
      (node (ref "C13") (pin "2") (pinfunction "2_2") (pintype "passive"))
      (node (ref "C14") (pin "1") (pinfunction "1_1") (pintype "passive"))
      (node (ref "C2") (pin "2") (pinfunction "2_2") (pintype "passive"))
      (node (ref "C3") (pin "2") (pinfunction "2_2") (pintype "passive"))
      (node (ref "C4") (pin "2") (pinfunction "2_2") (pintype "passive"))
      (node (ref "C5") (pin "2") (pinfunction "2_2") (pintype "passive"))
      (node (ref "C6") (pin "2") (pinfunction "2_2") (pintype "passive"))
      (node (ref "C7") (pin "2") (pinfunction "2_2") (pintype "passive"))
      (node (ref "C8") (pin "2") (pinfunction "2_2") (pintype "passive"))
      (node (ref "C9") (pin "2") (pinfunction "2_2") (pintype "passive"))
      (node (ref "D26") (pin "1") (pinfunction "A_1") (pintype "passive"))
      (node (ref "D27") (pin "1") (pinfunction "A_1") (pintype "passive"))
      (node (ref "D28") (pin "1") (pinfunction "A_1") (pintype "passive"))
      (node (ref "D7") (pin "1") (pinfunction "A_1") (pintype "passive"))
      (node (ref "L15") (pin "1") (pinfunction "1_1") (pintype "passive"))
      (node (ref "L8") (pin "2") (pinfunction "2_2") (pintype "passive"))
      (node (ref "P4") (pin "3") (pinfunction "3_3") (pintype "passive"))
      (node (ref "P5") (pin "3") (pinfunction "3_3") (pintype "passive"))
      (node (ref "U1") (pin "30") (pinfunction "V-_30") (pintype "passive"))
      (node (ref "U1") (pin "31") (pinfunction "NC_31") (pintype "passive"))
      (node (ref "U1") (pin "32") (pinfunction "VTEMP1_32") (pintype "passive"))
      (node (ref "U1") (pin "33") (pinfunction "VTEMP2_33") (pintype "passive"))
    )
    (net (code "47") (name "Net-(D1-A)") (class "Default")
      (node (ref "D1") (pin "1") (pinfunction "A_1") (pintype "passive"))
      (node (ref "Q1") (pin "2") (pinfunction "2_2") (pintype "passive"))
      (node (ref "R1") (pin "2") (pinfunction "2_2") (pintype "passive"))
    )
    (net (code "48") (name "Net-(D1-K)") (class "Default")
      (node (ref "D1") (pin "2") (pinfunction "K_2") (pintype "passive"))
      (node (ref "R7") (pin "2") (pinfunction "2_2") (pintype "passive"))
    )
    (net (code "49") (name "Net-(D2-A)") (class "Default")
      (node (ref "D2") (pin "1") (pinfunction "A_1") (pintype "passive"))
      (node (ref "Q2") (pin "2") (pinfunction "2_2") (pintype "passive"))
      (node (ref "R2") (pin "2") (pinfunction "2_2") (pintype "passive"))
    )
    (net (code "50") (name "Net-(D2-K)") (class "Default")
      (node (ref "D2") (pin "2") (pinfunction "K_2") (pintype "passive"))
      (node (ref "R8") (pin "2") (pinfunction "2_2") (pintype "passive"))
    )
    (net (code "51") (name "Net-(D3-A)") (class "Default")
      (node (ref "D3") (pin "1") (pinfunction "A_1") (pintype "passive"))
      (node (ref "Q3") (pin "2") (pinfunction "2_2") (pintype "passive"))
      (node (ref "R3") (pin "2") (pinfunction "2_2") (pintype "passive"))
    )
    (net (code "52") (name "Net-(D3-K)") (class "Default")
      (node (ref "D3") (pin "2") (pinfunction "K_2") (pintype "passive"))
      (node (ref "R9") (pin "2") (pinfunction "2_2") (pintype "passive"))
    )
    (net (code "53") (name "Net-(D4-A)") (class "Default")
      (node (ref "D4") (pin "1") (pinfunction "A_1") (pintype "passive"))
      (node (ref "Q4") (pin "2") (pinfunction "2_2") (pintype "passive"))
      (node (ref "R4") (pin "2") (pinfunction "2_2") (pintype "passive"))
    )
    (net (code "54") (name "Net-(D4-K)") (class "Default")
      (node (ref "D4") (pin "2") (pinfunction "K_2") (pintype "passive"))
      (node (ref "R10") (pin "2") (pinfunction "2_2") (pintype "passive"))
    )
    (net (code "55") (name "Net-(D5-A)") (class "Default")
      (node (ref "D5") (pin "1") (pinfunction "A_1") (pintype "passive"))
      (node (ref "Q5") (pin "2") (pinfunction "2_2") (pintype "passive"))
      (node (ref "R5") (pin "2") (pinfunction "2_2") (pintype "passive"))
    )
    (net (code "56") (name "Net-(D5-K)") (class "Default")
      (node (ref "D5") (pin "2") (pinfunction "K_2") (pintype "passive"))
      (node (ref "R11") (pin "2") (pinfunction "2_2") (pintype "passive"))
    )
    (net (code "57") (name "Net-(D6-A)") (class "Default")
      (node (ref "D6") (pin "1") (pinfunction "A_1") (pintype "passive"))
      (node (ref "Q6") (pin "2") (pinfunction "2_2") (pintype "passive"))
      (node (ref "R6") (pin "2") (pinfunction "2_2") (pintype "passive"))
    )
    (net (code "58") (name "Net-(D6-K)") (class "Default")
      (node (ref "D6") (pin "2") (pinfunction "K_2") (pintype "passive"))
      (node (ref "R12") (pin "2") (pinfunction "2_2") (pintype "passive"))
    )
    (net (code "59") (name "Net-(D14-A)") (class "Default")
      (node (ref "D14") (pin "1") (pinfunction "A_1") (pintype "passive"))
      (node (ref "Q7") (pin "2") (pinfunction "2_2") (pintype "passive"))
      (node (ref "R26") (pin "2") (pinfunction "2_2") (pintype "passive"))
    )
    (net (code "60") (name "Net-(D14-K)") (class "Default")
      (node (ref "D14") (pin "2") (pinfunction "K_2") (pintype "passive"))
      (node (ref "R32") (pin "2") (pinfunction "2_2") (pintype "passive"))
    )
    (net (code "61") (name "Net-(D15-A)") (class "Default")
      (node (ref "D15") (pin "1") (pinfunction "A_1") (pintype "passive"))
      (node (ref "Q8") (pin "2") (pinfunction "2_2") (pintype "passive"))
      (node (ref "R27") (pin "2") (pinfunction "2_2") (pintype "passive"))
    )
    (net (code "62") (name "Net-(D15-K)") (class "Default")
      (node (ref "D15") (pin "2") (pinfunction "K_2") (pintype "passive"))
      (node (ref "R33") (pin "2") (pinfunction "2_2") (pintype "passive"))
    )
    (net (code "63") (name "Net-(D16-A)") (class "Default")
      (node (ref "D16") (pin "1") (pinfunction "A_1") (pintype "passive"))
      (node (ref "Q9") (pin "2") (pinfunction "2_2") (pintype "passive"))
      (node (ref "R28") (pin "2") (pinfunction "2_2") (pintype "passive"))
    )
    (net (code "64") (name "Net-(D16-K)") (class "Default")
      (node (ref "D16") (pin "2") (pinfunction "K_2") (pintype "passive"))
      (node (ref "R34") (pin "2") (pinfunction "2_2") (pintype "passive"))
    )
    (net (code "65") (name "Net-(D17-A)") (class "Default")
      (node (ref "D17") (pin "1") (pinfunction "A_1") (pintype "passive"))
      (node (ref "R29") (pin "2") (pinfunction "2_2") (pintype "passive"))
    )
    (net (code "66") (name "Net-(D17-K)") (class "Default")
      (node (ref "D17") (pin "2") (pinfunction "K_2") (pintype "passive"))
      (node (ref "R35") (pin "2") (pinfunction "2_2") (pintype "passive"))
    )
    (net (code "67") (name "Net-(D18-A)") (class "Default")
      (node (ref "D18") (pin "1") (pinfunction "A_1") (pintype "passive"))
      (node (ref "Q11") (pin "2") (pinfunction "2_2") (pintype "passive"))
      (node (ref "R30") (pin "2") (pinfunction "2_2") (pintype "passive"))
    )
    (net (code "68") (name "Net-(D18-K)") (class "Default")
      (node (ref "D18") (pin "2") (pinfunction "K_2") (pintype "passive"))
      (node (ref "R36") (pin "2") (pinfunction "2_2") (pintype "passive"))
    )
    (net (code "69") (name "Net-(D19-A)") (class "Default")
      (node (ref "D19") (pin "1") (pinfunction "A_1") (pintype "passive"))
      (node (ref "Q12") (pin "2") (pinfunction "2_2") (pintype "passive"))
      (node (ref "R31") (pin "2") (pinfunction "2_2") (pintype "passive"))
    )
    (net (code "70") (name "Net-(D19-K)") (class "Default")
      (node (ref "D19") (pin "2") (pinfunction "K_2") (pintype "passive"))
      (node (ref "R37") (pin "2") (pinfunction "2_2") (pintype "passive"))
    )
    (net (code "71") (name "Net-(D26-K)") (class "Default")
      (node (ref "D26") (pin "2") (pinfunction "K_2") (pintype "passive"))
      (node (ref "D27") (pin "2") (pinfunction "K_2") (pintype "passive"))
      (node (ref "D28") (pin "2") (pinfunction "K_2") (pintype "passive"))
      (node (ref "R50") (pin "2") (pinfunction "2_2") (pintype "passive"))
    )
    (net (code "72") (name "Net-(D29-K)") (class "Default")
      (node (ref "D29") (pin "2") (pinfunction "K_2") (pintype "passive"))
      (node (ref "R51") (pin "2") (pinfunction "2_2") (pintype "passive"))
    )
    (net (code "73") (name "Net-(D30-K)") (class "Default")
      (node (ref "D30") (pin "2") (pinfunction "K_2") (pintype "passive"))
      (node (ref "R52") (pin "2") (pinfunction "2_2") (pintype "passive"))
    )
    (net (code "74") (name "Net-(D31-K)") (class "Default")
      (node (ref "D31") (pin "2") (pinfunction "K_2") (pintype "passive"))
      (node (ref "R53") (pin "2") (pinfunction "2_2") (pintype "passive"))
    )
    (net (code "75") (name "Net-(L1-Pad1)") (class "Default")
      (node (ref "L1") (pin "1") (pinfunction "1_1") (pintype "passive"))
      (node (ref "Q1") (pin "3") (pinfunction "3_3") (pintype "passive"))
      (node (ref "R14") (pin "1") (pinfunction "1_1") (pintype "passive"))
      (node (ref "R2") (pin "1") (pinfunction "1_1") (pintype "passive"))
      (node (ref "R8") (pin "1") (pinfunction "1_1") (pintype "passive"))
    )
    (net (code "76") (name "Net-(L2-Pad1)") (class "Default")
      (node (ref "L2") (pin "1") (pinfunction "1_1") (pintype "passive"))
      (node (ref "Q2") (pin "3") (pinfunction "3_3") (pintype "passive"))
      (node (ref "R16") (pin "1") (pinfunction "1_1") (pintype "passive"))
      (node (ref "R3") (pin "1") (pinfunction "1_1") (pintype "passive"))
      (node (ref "R9") (pin "1") (pinfunction "1_1") (pintype "passive"))
    )
    (net (code "77") (name "Net-(L3-Pad1)") (class "Default")
      (node (ref "L3") (pin "1") (pinfunction "1_1") (pintype "passive"))
      (node (ref "Q3") (pin "3") (pinfunction "3_3") (pintype "passive"))
      (node (ref "R10") (pin "1") (pinfunction "1_1") (pintype "passive"))
      (node (ref "R18") (pin "1") (pinfunction "1_1") (pintype "passive"))
      (node (ref "R4") (pin "1") (pinfunction "1_1") (pintype "passive"))
    )
    (net (code "78") (name "Net-(L4-Pad1)") (class "Default")
      (node (ref "L4") (pin "1") (pinfunction "1_1") (pintype "passive"))
      (node (ref "Q4") (pin "3") (pinfunction "3_3") (pintype "passive"))
      (node (ref "R11") (pin "1") (pinfunction "1_1") (pintype "passive"))
      (node (ref "R20") (pin "1") (pinfunction "1_1") (pintype "passive"))
      (node (ref "R5") (pin "1") (pinfunction "1_1") (pintype "passive"))
    )
    (net (code "79") (name "Net-(L5-Pad1)") (class "Default")
      (node (ref "L5") (pin "1") (pinfunction "1_1") (pintype "passive"))
      (node (ref "Q5") (pin "3") (pinfunction "3_3") (pintype "passive"))
      (node (ref "R12") (pin "1") (pinfunction "1_1") (pintype "passive"))
      (node (ref "R22") (pin "1") (pinfunction "1_1") (pintype "passive"))
      (node (ref "R6") (pin "1") (pinfunction "1_1") (pintype "passive"))
    )
    (net (code "80") (name "Net-(L6-Pad1)") (class "Default")
      (node (ref "L6") (pin "1") (pinfunction "1_1") (pintype "passive"))
      (node (ref "Q6") (pin "3") (pinfunction "3_3") (pintype "passive"))
      (node (ref "R24") (pin "1") (pinfunction "1_1") (pintype "passive"))
      (node (ref "R26") (pin "1") (pinfunction "1_1") (pintype "passive"))
      (node (ref "R32") (pin "1") (pinfunction "1_1") (pintype "passive"))
    )
    (net (code "81") (name "Net-(L7-Pad2)") (class "Default")
      (node (ref "L7") (pin "2") (pinfunction "2_2") (pintype "passive"))
      (node (ref "R1") (pin "1") (pinfunction "1_1") (pintype "passive"))
      (node (ref "R13") (pin "1") (pinfunction "1_1") (pintype "passive"))
      (node (ref "R7") (pin "1") (pinfunction "1_1") (pintype "passive"))
    )
    (net (code "82") (name "Net-(L9-Pad1)") (class "Default")
      (node (ref "L9") (pin "1") (pinfunction "1_1") (pintype "passive"))
      (node (ref "Q7") (pin "3") (pinfunction "3_3") (pintype "passive"))
      (node (ref "R27") (pin "1") (pinfunction "1_1") (pintype "passive"))
      (node (ref "R33") (pin "1") (pinfunction "1_1") (pintype "passive"))
      (node (ref "R38") (pin "1") (pinfunction "1_1") (pintype "passive"))
    )
    (net (code "83") (name "Net-(L10-Pad1)") (class "Default")
      (node (ref "L10") (pin "1") (pinfunction "1_1") (pintype "passive"))
      (node (ref "Q8") (pin "3") (pinfunction "3_3") (pintype "passive"))
      (node (ref "R28") (pin "1") (pinfunction "1_1") (pintype "passive"))
      (node (ref "R34") (pin "1") (pinfunction "1_1") (pintype "passive"))
      (node (ref "R40") (pin "1") (pinfunction "1_1") (pintype "passive"))
    )
    (net (code "84") (name "Net-(L11-Pad1)") (class "Default")
      (node (ref "L11") (pin "1") (pinfunction "1_1") (pintype "passive"))
      (node (ref "Q9") (pin "3") (pinfunction "3_3") (pintype "passive"))
      (node (ref "R29") (pin "1") (pinfunction "1_1") (pintype "passive"))
      (node (ref "R35") (pin "1") (pinfunction "1_1") (pintype "passive"))
      (node (ref "R42") (pin "1") (pinfunction "1_1") (pintype "passive"))
    )
    (net (code "85") (name "Net-(L12-Pad1)") (class "Default")
      (node (ref "L12") (pin "1") (pinfunction "1_1") (pintype "passive"))
      (node (ref "R30") (pin "1") (pinfunction "1_1") (pintype "passive"))
      (node (ref "R36") (pin "1") (pinfunction "1_1") (pintype "passive"))
      (node (ref "R44") (pin "1") (pinfunction "1_1") (pintype "passive"))
    )
    (net (code "86") (name "Net-(L13-Pad1)") (class "Default")
      (node (ref "L13") (pin "1") (pinfunction "1_1") (pintype "passive"))
      (node (ref "Q11") (pin "3") (pinfunction "3_3") (pintype "passive"))
      (node (ref "R31") (pin "1") (pinfunction "1_1") (pintype "passive"))
      (node (ref "R37") (pin "1") (pinfunction "1_1") (pintype "passive"))
      (node (ref "R46") (pin "1") (pinfunction "1_1") (pintype "passive"))
    )
    (net (code "87") (name "Net-(L14-Pad1)") (class "Default")
      (node (ref "L14") (pin "1") (pinfunction "1_1") (pintype "passive"))
      (node (ref "Q12") (pin "3") (pinfunction "3_3") (pintype "passive"))
      (node (ref "R48") (pin "1") (pinfunction "1_1") (pintype "passive"))
    )
    (net (code "88") (name "Net-(P4-Pad2)") (class "Default")
      (node (ref "P4") (pin "2") (pinfunction "2_2") (pintype "passive"))
      (node (ref "R63") (pin "1") (pinfunction "1_1") (pintype "passive"))
    )
    (net (code "89") (name "Net-(P5-Pad2)") (class "Default")
      (node (ref "P5") (pin "2") (pinfunction "2_2") (pintype "passive"))
      (node (ref "R61") (pin "1") (pinfunction "1_1") (pintype "passive"))
    )
    (net (code "90") (name "Net-(Q1-G)") (class "Default")
      (node (ref "Q1") (pin "1") (pinfunction "G_1") (pintype "passive"))
      (node (ref "R15") (pin "1") (pinfunction "1_1") (pintype "passive"))
    )
    (net (code "91") (name "Net-(Q2-G)") (class "Default")
      (node (ref "Q2") (pin "1") (pinfunction "G_1") (pintype "passive"))
      (node (ref "R17") (pin "1") (pinfunction "1_1") (pintype "passive"))
    )
    (net (code "92") (name "Net-(Q3-G)") (class "Default")
      (node (ref "Q3") (pin "1") (pinfunction "G_1") (pintype "passive"))
      (node (ref "R19") (pin "1") (pinfunction "1_1") (pintype "passive"))
    )
    (net (code "93") (name "Net-(Q4-G)") (class "Default")
      (node (ref "Q4") (pin "1") (pinfunction "G_1") (pintype "passive"))
      (node (ref "R21") (pin "1") (pinfunction "1_1") (pintype "passive"))
    )
    (net (code "94") (name "Net-(Q5-G)") (class "Default")
      (node (ref "Q5") (pin "1") (pinfunction "G_1") (pintype "passive"))
      (node (ref "R23") (pin "1") (pinfunction "1_1") (pintype "passive"))
    )
    (net (code "95") (name "Net-(Q6-G)") (class "Default")
      (node (ref "Q6") (pin "1") (pinfunction "G_1") (pintype "passive"))
      (node (ref "R25") (pin "1") (pinfunction "1_1") (pintype "passive"))
    )
    (net (code "96") (name "Net-(Q7-G)") (class "Default")
      (node (ref "Q7") (pin "1") (pinfunction "G_1") (pintype "passive"))
      (node (ref "R39") (pin "1") (pinfunction "1_1") (pintype "passive"))
    )
    (net (code "97") (name "Net-(Q8-G)") (class "Default")
      (node (ref "Q8") (pin "1") (pinfunction "G_1") (pintype "passive"))
      (node (ref "R41") (pin "1") (pinfunction "1_1") (pintype "passive"))
    )
    (net (code "98") (name "Net-(Q9-G)") (class "Default")
      (node (ref "Q9") (pin "1") (pinfunction "G_1") (pintype "passive"))
      (node (ref "R43") (pin "1") (pinfunction "1_1") (pintype "passive"))
    )
    (net (code "99") (name "Net-(Q10-Pad3)") (class "Default")
      (node (ref "Q10") (pin "3") (pinfunction "3_3") (pintype "passive"))
      (node (ref "R45") (pin "1") (pinfunction "1_1") (pintype "passive"))
    )
    (net (code "100") (name "Net-(Q11-G)") (class "Default")
      (node (ref "Q11") (pin "1") (pinfunction "G_1") (pintype "passive"))
      (node (ref "R47") (pin "1") (pinfunction "1_1") (pintype "passive"))
    )
    (net (code "101") (name "Net-(Q12-G)") (class "Default")
      (node (ref "Q12") (pin "1") (pinfunction "G_1") (pintype "passive"))
      (node (ref "R49") (pin "1") (pinfunction "1_1") (pintype "passive"))
    )
    (net (code "102") (name "Net-(U1-CSBI)") (class "Default")
      (node (ref "R57") (pin "2") (pinfunction "2_2") (pintype "passive"))
      (node (ref "U1") (pin "44") (pinfunction "CSBI_44") (pintype "passive"))
    )
    (net (code "103") (name "Net-(U1-CSBO)") (class "Default")
      (node (ref "R53") (pin "1") (pinfunction "1_1") (pintype "passive"))
      (node (ref "U1") (pin "1") (pinfunction "CSBO_1") (pintype "passive"))
    )
    (net (code "104") (name "Net-(U1-GPIO1)") (class "Default")
      (node (ref "R55") (pin "2") (pinfunction "2_2") (pintype "passive"))
      (node (ref "U1") (pin "38") (pinfunction "GPIO1_38") (pintype "passive"))
    )
    (net (code "105") (name "Net-(U1-GPIO2)") (class "Default")
      (node (ref "R56") (pin "2") (pinfunction "2_2") (pintype "passive"))
      (node (ref "U1") (pin "39") (pinfunction "GPIO2_39") (pintype "passive"))
    )
    (net (code "106") (name "Net-(U1-SCKI)") (class "Default")
      (node (ref "R62") (pin "2") (pinfunction "2_2") (pintype "passive"))
      (node (ref "U1") (pin "41") (pinfunction "SCKI_41") (pintype "passive"))
    )
    (net (code "107") (name "Net-(U1-SCKO)") (class "Default")
      (node (ref "R51") (pin "1") (pinfunction "1_1") (pintype "passive"))
      (node (ref "U1") (pin "3") (pinfunction "SCKO_3") (pintype "passive"))
    )
    (net (code "108") (name "Net-(U1-SDI)") (class "Default")
      (node (ref "R60") (pin "2") (pinfunction "2_2") (pintype "passive"))
      (node (ref "U1") (pin "42") (pinfunction "SDI_42") (pintype "passive"))
    )
    (net (code "109") (name "Net-(U1-SDO)") (class "Default")
      (node (ref "R58") (pin "2") (pinfunction "2_2") (pintype "passive"))
      (node (ref "U1") (pin "43") (pinfunction "SDO_43") (pintype "passive"))
    )
    (net (code "110") (name "Net-(U1-SDOI)") (class "Default")
      (node (ref "R52") (pin "1") (pinfunction "1_1") (pintype "passive"))
      (node (ref "U1") (pin "2") (pinfunction "SDOI_2") (pintype "passive"))
    )
    (net (code "111") (name "Net-(U1-TOS)") (class "Default")
      (node (ref "R63") (pin "2") (pinfunction "2_2") (pintype "passive"))
      (node (ref "U1") (pin "36") (pinfunction "TOS_36") (pintype "passive"))
    )
    (net (code "112") (name "Net-(U1-V+)") (class "Default")
      (node (ref "C14") (pin "2") (pinfunction "2_2") (pintype "passive"))
      (node (ref "R50") (pin "1") (pinfunction "1_1") (pintype "passive"))
      (node (ref "U1") (pin "4") (pinfunction "V+_4") (pintype "passive"))
    )
    (net (code "113") (name "Net-(U1-VMODE)") (class "Default")
      (node (ref "R61") (pin "2") (pinfunction "2_2") (pintype "passive"))
      (node (ref "U1") (pin "40") (pinfunction "VMODE_40") (pintype "passive"))
    )
    (net (code "114") (name "Net-(U1-WDTB)") (class "Default")
      (node (ref "R54") (pin "2") (pinfunction "2_2") (pintype "passive"))
      (node (ref "U1") (pin "37") (pinfunction "WDTB_37") (pintype "passive"))
    )
    (net (code "115") (name "VREG") (class "Default")
      (node (ref "P4") (pin "1") (pinfunction "1_1") (pintype "passive"))
      (node (ref "P5") (pin "1") (pinfunction "1_1") (pintype "passive"))
      (node (ref "R54") (pin "1") (pinfunction "1_1") (pintype "passive"))
      (node (ref "R55") (pin "1") (pinfunction "1_1") (pintype "passive"))
      (node (ref "R56") (pin "1") (pinfunction "1_1") (pintype "passive"))
      (node (ref "R59") (pin "1") (pinfunction "1_1") (pintype "passive"))
      (node (ref "R64") (pin "1") (pinfunction "1_1") (pintype "passive"))
      (node (ref "R65") (pin "1") (pinfunction "1_1") (pintype "passive"))
      (node (ref "U1") (pin "35") (pinfunction "VREG_35") (pintype "passive"))
    )
    (net (code "116") (name "unconnected-(P2-Pad2)") (class "Default")
      (node (ref "P2") (pin "2") (pinfunction "2_2") (pintype "passive+no_connect"))
    )
    (net (code "117") (name "unconnected-(Q10-G-Pad1)") (class "Default")
      (node (ref "Q10") (pin "1") (pinfunction "G_1") (pintype "passive"))
    )
    (net (code "118") (name "unconnected-(Q10-Pad2)") (class "Default")
      (node (ref "Q10") (pin "2") (pinfunction "2_2") (pintype "passive"))
    )
    (net (code "119") (name "unconnected-(U1-VREF-Pad34)") (class "Default")
      (node (ref "U1") (pin "34") (pinfunction "VREF_34") (pintype "passive+no_connect"))
    )
  )
)
